# AT42QT1070_Acorn.net
KiCad netlist of a schematic drawn in EAGLE
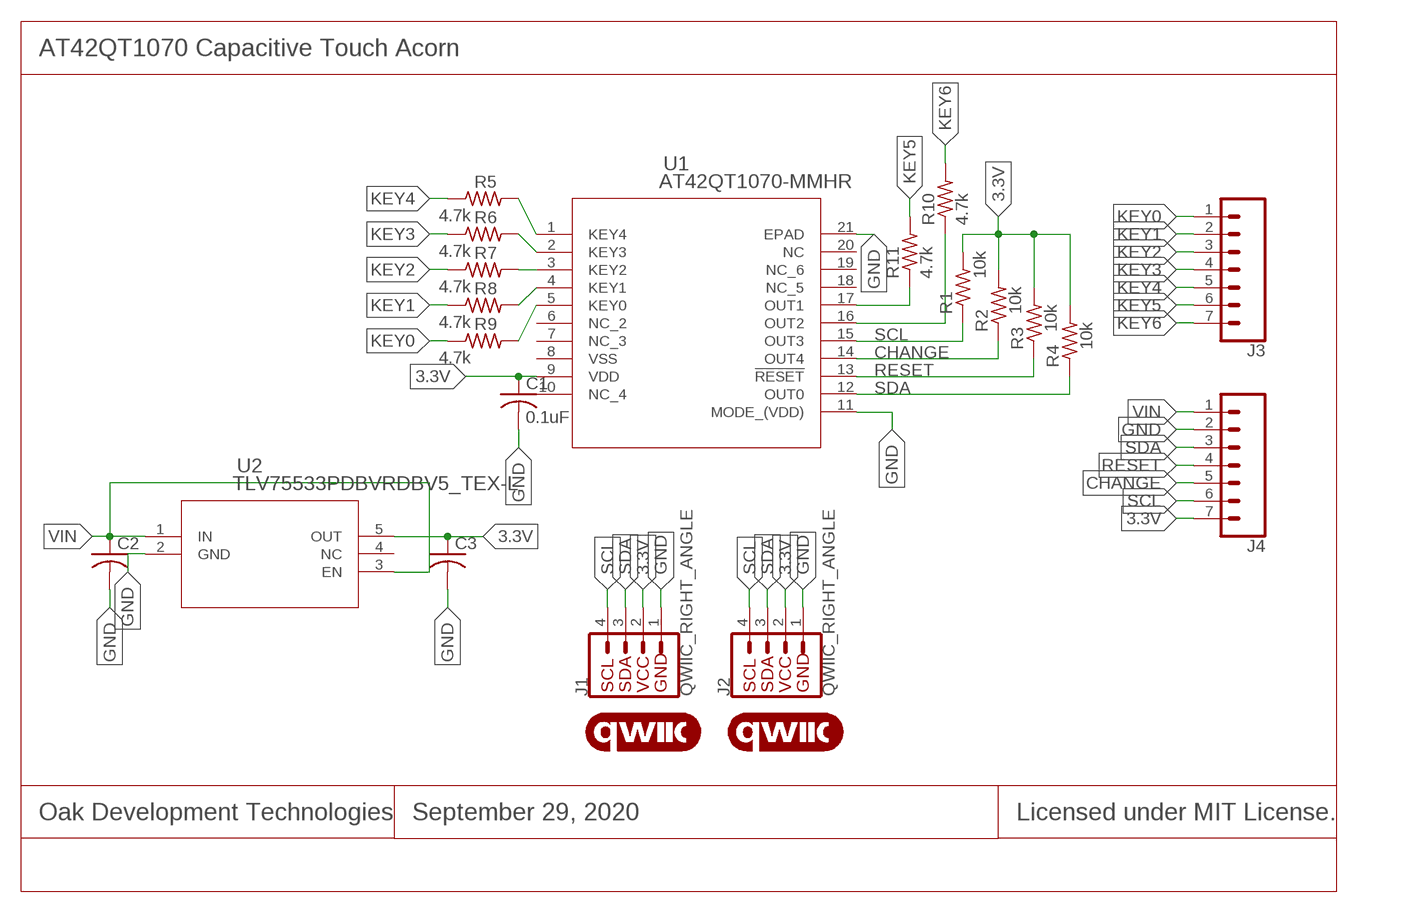
[diagram p0: schematic, sheet 1]

(export (version "E")
  (design (tool "Eeschema 10.0.6"))
  (components
    (comp (ref "C1")
      (value "0.1uF")
      (footprint "eagle-import:C0402")
      (libsource (lib "eagle-import") (part "C-USC0402"))
    )
    (comp (ref "C2")
      (value "C-USC0402")
      (footprint "eagle-import:C0402")
      (libsource (lib "eagle-import") (part "C-USC0402"))
    )
    (comp (ref "C3")
      (value "C-USC0402")
      (footprint "eagle-import:C0402")
      (libsource (lib "eagle-import") (part "C-USC0402"))
    )
    (comp (ref "J1")
      (value "QWIIC_RIGHT_ANGLE")
      (footprint "eagle-import:JST04_1MM_RA")
      (libsource (lib "eagle-import") (part "QWIIC_CONNECTORJS-1MM"))
    )
    (comp (ref "J2")
      (value "QWIIC_RIGHT_ANGLE")
      (footprint "eagle-import:JST04_1MM_RA")
      (libsource (lib "eagle-import") (part "QWIIC_CONNECTORJS-1MM"))
    )
    (comp (ref "J3")
      (value "CONN_07NO_SILK")
      (footprint "eagle-import:1X07_NO_SILK")
      (libsource (lib "eagle-import") (part "CONN_07NO_SILK"))
    )
    (comp (ref "J4")
      (value "CONN_07NO_SILK")
      (footprint "eagle-import:1X07_NO_SILK")
      (libsource (lib "eagle-import") (part "CONN_07NO_SILK"))
    )
    (comp (ref "LOGO1")
      (value "QWIIC_LOGO_6MM")
      (footprint "eagle-import:QWIIC_6MM")
      (libsource (lib "eagle-import") (part "QWIIC_LOGO_6MM"))
    )
    (comp (ref "LOGO2")
      (value "QWIIC_LOGO_6MM")
      (footprint "eagle-import:QWIIC_6MM")
      (libsource (lib "eagle-import") (part "QWIIC_LOGO_6MM"))
    )
    (comp (ref "R1")
      (value "10k")
      (footprint "eagle-import:R0402")
      (libsource (lib "eagle-import") (part "R-US_R0402"))
    )
    (comp (ref "R2")
      (value "10k")
      (footprint "eagle-import:R0402")
      (libsource (lib "eagle-import") (part "R-US_R0402"))
    )
    (comp (ref "R3")
      (value "10k")
      (footprint "eagle-import:R0402")
      (libsource (lib "eagle-import") (part "R-US_R0402"))
    )
    (comp (ref "R4")
      (value "10k")
      (footprint "eagle-import:R0402")
      (libsource (lib "eagle-import") (part "R-US_R0402"))
    )
    (comp (ref "R5")
      (value "4.7k")
      (footprint "eagle-import:R0402")
      (libsource (lib "eagle-import") (part "R-US_R0402"))
    )
    (comp (ref "R6")
      (value "4.7k")
      (footprint "eagle-import:R0402")
      (libsource (lib "eagle-import") (part "R-US_R0402"))
    )
    (comp (ref "R7")
      (value "4.7k")
      (footprint "eagle-import:R0402")
      (libsource (lib "eagle-import") (part "R-US_R0402"))
    )
    (comp (ref "R8")
      (value "4.7k")
      (footprint "eagle-import:R0402")
      (libsource (lib "eagle-import") (part "R-US_R0402"))
    )
    (comp (ref "R9")
      (value "4.7k")
      (footprint "eagle-import:R0402")
      (libsource (lib "eagle-import") (part "R-US_R0402"))
    )
    (comp (ref "R10")
      (value "4.7k")
      (footprint "eagle-import:R0402")
      (libsource (lib "eagle-import") (part "R-US_R0402"))
    )
    (comp (ref "R11")
      (value "4.7k")
      (footprint "eagle-import:R0402")
      (libsource (lib "eagle-import") (part "R-US_R0402"))
    )
    (comp (ref "U1")
      (value "AT42QT1070-MMHR")
      (footprint "eagle-import:VQFN20_3X3_MCH")
      (fields (field (name "COPYRIGHT") "Copyright (C) 2018 Accelerated Designs. All rights reserved"))
      (libsource (lib "eagle-import") (part "AT42QT1070-MMHR"))
    )
    (comp (ref "U2")
      (value "TLV75533PDBVRDBV5_TEX-L")
      (footprint "eagle-import:DBV5_TEX-L")
      (fields
        (field (name "MANUFACTURER_PART_NUMBER") "TLV75533PDBVR")
        (field (name "COPYRIGHT") "Copyright (C) 2018 Accelerated Designs. All rights reserved")
      )
      (libsource (lib "eagle-import") (part "TLV75533PDBVRDBV5_TEX-L"))
    )
  )
  (nets
    (net (code "1") (name "3.3V") (class "Default")
      (node (ref "C1") (pin "1") (pinfunction "1_1") (pintype "passive"))
      (node (ref "C3") (pin "1") (pinfunction "1_1") (pintype "passive"))
      (node (ref "J1") (pin "2") (pinfunction "2_2") (pintype "power_in"))
      (node (ref "J2") (pin "2") (pinfunction "2_2") (pintype "power_in"))
      (node (ref "J4") (pin "7") (pinfunction "7_7") (pintype "passive"))
      (node (ref "R1") (pin "2") (pinfunction "2_2") (pintype "passive"))
      (node (ref "R2") (pin "2") (pinfunction "2_2") (pintype "passive"))
      (node (ref "R3") (pin "2") (pinfunction "2_2") (pintype "passive"))
      (node (ref "R4") (pin "2") (pinfunction "2_2") (pintype "passive"))
      (node (ref "U1") (pin "9") (pinfunction "VDD_9") (pintype "power_in"))
      (node (ref "U2") (pin "5") (pinfunction "OUT_5") (pintype "output"))
    )
    (net (code "2") (name "CHANGE") (class "Default")
      (node (ref "J4") (pin "5") (pinfunction "5_5") (pintype "passive"))
      (node (ref "R2") (pin "1") (pinfunction "1_1") (pintype "passive"))
      (node (ref "U1") (pin "14") (pinfunction "OUT4_14") (pintype "output"))
    )
    (net (code "3") (name "GND") (class "Default")
      (node (ref "C1") (pin "2") (pinfunction "2_2") (pintype "passive"))
      (node (ref "C2") (pin "2") (pinfunction "2_2") (pintype "passive"))
      (node (ref "C3") (pin "2") (pinfunction "2_2") (pintype "passive"))
      (node (ref "J1") (pin "1") (pinfunction "1_1") (pintype "power_in"))
      (node (ref "J2") (pin "1") (pinfunction "1_1") (pintype "power_in"))
      (node (ref "J4") (pin "2") (pinfunction "2_2") (pintype "passive"))
      (node (ref "U1") (pin "11") (pinfunction "MODE_(VDD)_11") (pintype "power_in"))
      (node (ref "U1") (pin "21") (pinfunction "EPAD_21") (pintype "passive"))
      (node (ref "U2") (pin "2") (pinfunction "GND_2") (pintype "power_in"))
    )
    (net (code "4") (name "KEY0") (class "Default")
      (node (ref "J3") (pin "1") (pinfunction "1_1") (pintype "passive"))
      (node (ref "R9") (pin "1") (pinfunction "1_1") (pintype "passive"))
    )
    (net (code "5") (name "KEY1") (class "Default")
      (node (ref "J3") (pin "2") (pinfunction "2_2") (pintype "passive"))
      (node (ref "R8") (pin "1") (pinfunction "1_1") (pintype "passive"))
    )
    (net (code "6") (name "KEY2") (class "Default")
      (node (ref "J3") (pin "3") (pinfunction "3_3") (pintype "passive"))
      (node (ref "R7") (pin "1") (pinfunction "1_1") (pintype "passive"))
    )
    (net (code "7") (name "KEY3") (class "Default")
      (node (ref "J3") (pin "4") (pinfunction "4_4") (pintype "passive"))
      (node (ref "R6") (pin "1") (pinfunction "1_1") (pintype "passive"))
    )
    (net (code "8") (name "KEY4") (class "Default")
      (node (ref "J3") (pin "5") (pinfunction "5_5") (pintype "passive"))
      (node (ref "R5") (pin "1") (pinfunction "1_1") (pintype "passive"))
    )
    (net (code "9") (name "KEY5") (class "Default")
      (node (ref "J3") (pin "6") (pinfunction "6_6") (pintype "passive"))
      (node (ref "R11") (pin "2") (pinfunction "2_2") (pintype "passive"))
    )
    (net (code "10") (name "KEY6") (class "Default")
      (node (ref "J3") (pin "7") (pinfunction "7_7") (pintype "passive"))
      (node (ref "R10") (pin "2") (pinfunction "2_2") (pintype "passive"))
    )
    (net (code "11") (name "Net-(U1-KEY0)") (class "Default")
      (node (ref "R9") (pin "2") (pinfunction "2_2") (pintype "passive"))
      (node (ref "U1") (pin "5") (pinfunction "KEY0_5") (pintype "bidirectional"))
    )
    (net (code "12") (name "Net-(U1-KEY1)") (class "Default")
      (node (ref "R8") (pin "2") (pinfunction "2_2") (pintype "passive"))
      (node (ref "U1") (pin "4") (pinfunction "KEY1_4") (pintype "bidirectional"))
    )
    (net (code "13") (name "Net-(U1-KEY2)") (class "Default")
      (node (ref "R7") (pin "2") (pinfunction "2_2") (pintype "passive"))
      (node (ref "U1") (pin "3") (pinfunction "KEY2_3") (pintype "bidirectional"))
    )
    (net (code "14") (name "Net-(U1-KEY3)") (class "Default")
      (node (ref "R6") (pin "2") (pinfunction "2_2") (pintype "passive"))
      (node (ref "U1") (pin "2") (pinfunction "KEY3_2") (pintype "bidirectional"))
    )
    (net (code "15") (name "Net-(U1-KEY4)") (class "Default")
      (node (ref "R5") (pin "2") (pinfunction "2_2") (pintype "passive"))
      (node (ref "U1") (pin "1") (pinfunction "KEY4_1") (pintype "bidirectional"))
    )
    (net (code "16") (name "Net-(U1-OUT1)") (class "Default")
      (node (ref "R11") (pin "1") (pinfunction "1_1") (pintype "passive"))
      (node (ref "U1") (pin "17") (pinfunction "OUT1_17") (pintype "output"))
    )
    (net (code "17") (name "Net-(U1-OUT2)") (class "Default")
      (node (ref "R10") (pin "1") (pinfunction "1_1") (pintype "passive"))
      (node (ref "U1") (pin "16") (pinfunction "OUT2_16") (pintype "output"))
    )
    (net (code "18") (name "RESET") (class "Default")
      (node (ref "J4") (pin "4") (pinfunction "4_4") (pintype "passive"))
      (node (ref "R3") (pin "1") (pinfunction "1_1") (pintype "passive"))
      (node (ref "U1") (pin "13") (pinfunction "~{RESET}_13") (pintype "passive"))
    )
    (net (code "19") (name "SCL") (class "Default")
      (node (ref "J1") (pin "4") (pinfunction "4_4") (pintype "passive"))
      (node (ref "J2") (pin "4") (pinfunction "4_4") (pintype "passive"))
      (node (ref "J4") (pin "6") (pinfunction "6_6") (pintype "passive"))
      (node (ref "R1") (pin "1") (pinfunction "1_1") (pintype "passive"))
      (node (ref "U1") (pin "15") (pinfunction "OUT3_15") (pintype "output"))
    )
    (net (code "20") (name "SDA") (class "Default")
      (node (ref "J1") (pin "3") (pinfunction "3_3") (pintype "passive"))
      (node (ref "J2") (pin "3") (pinfunction "3_3") (pintype "passive"))
      (node (ref "J4") (pin "3") (pinfunction "3_3") (pintype "passive"))
      (node (ref "R4") (pin "1") (pinfunction "1_1") (pintype "passive"))
      (node (ref "U1") (pin "12") (pinfunction "OUT0_12") (pintype "output"))
    )
    (net (code "21") (name "VIN") (class "Default")
      (node (ref "C2") (pin "1") (pinfunction "1_1") (pintype "passive"))
      (node (ref "J4") (pin "1") (pinfunction "1_1") (pintype "passive"))
      (node (ref "U2") (pin "1") (pinfunction "IN_1") (pintype "input"))
      (node (ref "U2") (pin "3") (pinfunction "EN_3") (pintype "input"))
    )
    (net (code "22") (name "unconnected-(U1-NC-Pad20)") (class "Default")
      (node (ref "U1") (pin "20") (pinfunction "NC_20") (pintype "no_connect"))
    )
    (net (code "23") (name "unconnected-(U1-NC_2-Pad6)") (class "Default")
      (node (ref "U1") (pin "6") (pinfunction "NC_2_6") (pintype "no_connect"))
    )
    (net (code "24") (name "unconnected-(U1-NC_3-Pad7)") (class "Default")
      (node (ref "U1") (pin "7") (pinfunction "NC_3_7") (pintype "no_connect"))
    )
    (net (code "25") (name "unconnected-(U1-NC_4-Pad10)") (class "Default")
      (node (ref "U1") (pin "10") (pinfunction "NC_4_10") (pintype "no_connect"))
    )
    (net (code "26") (name "unconnected-(U1-NC_5-Pad18)") (class "Default")
      (node (ref "U1") (pin "18") (pinfunction "NC_5_18") (pintype "no_connect"))
    )
    (net (code "27") (name "unconnected-(U1-NC_6-Pad19)") (class "Default")
      (node (ref "U1") (pin "19") (pinfunction "NC_6_19") (pintype "no_connect"))
    )
    (net (code "28") (name "unconnected-(U1-VSS-Pad8)") (class "Default")
      (node (ref "U1") (pin "8") (pinfunction "VSS_8") (pintype "passive"))
    )
    (net (code "29") (name "unconnected-(U2-NC-Pad4)") (class "Default")
      (node (ref "U2") (pin "4") (pinfunction "NC_4") (pintype "no_connect"))
    )
  )
)
